# LANTERN_4LED.net
KiCad netlist of a schematic drawn in EAGLE
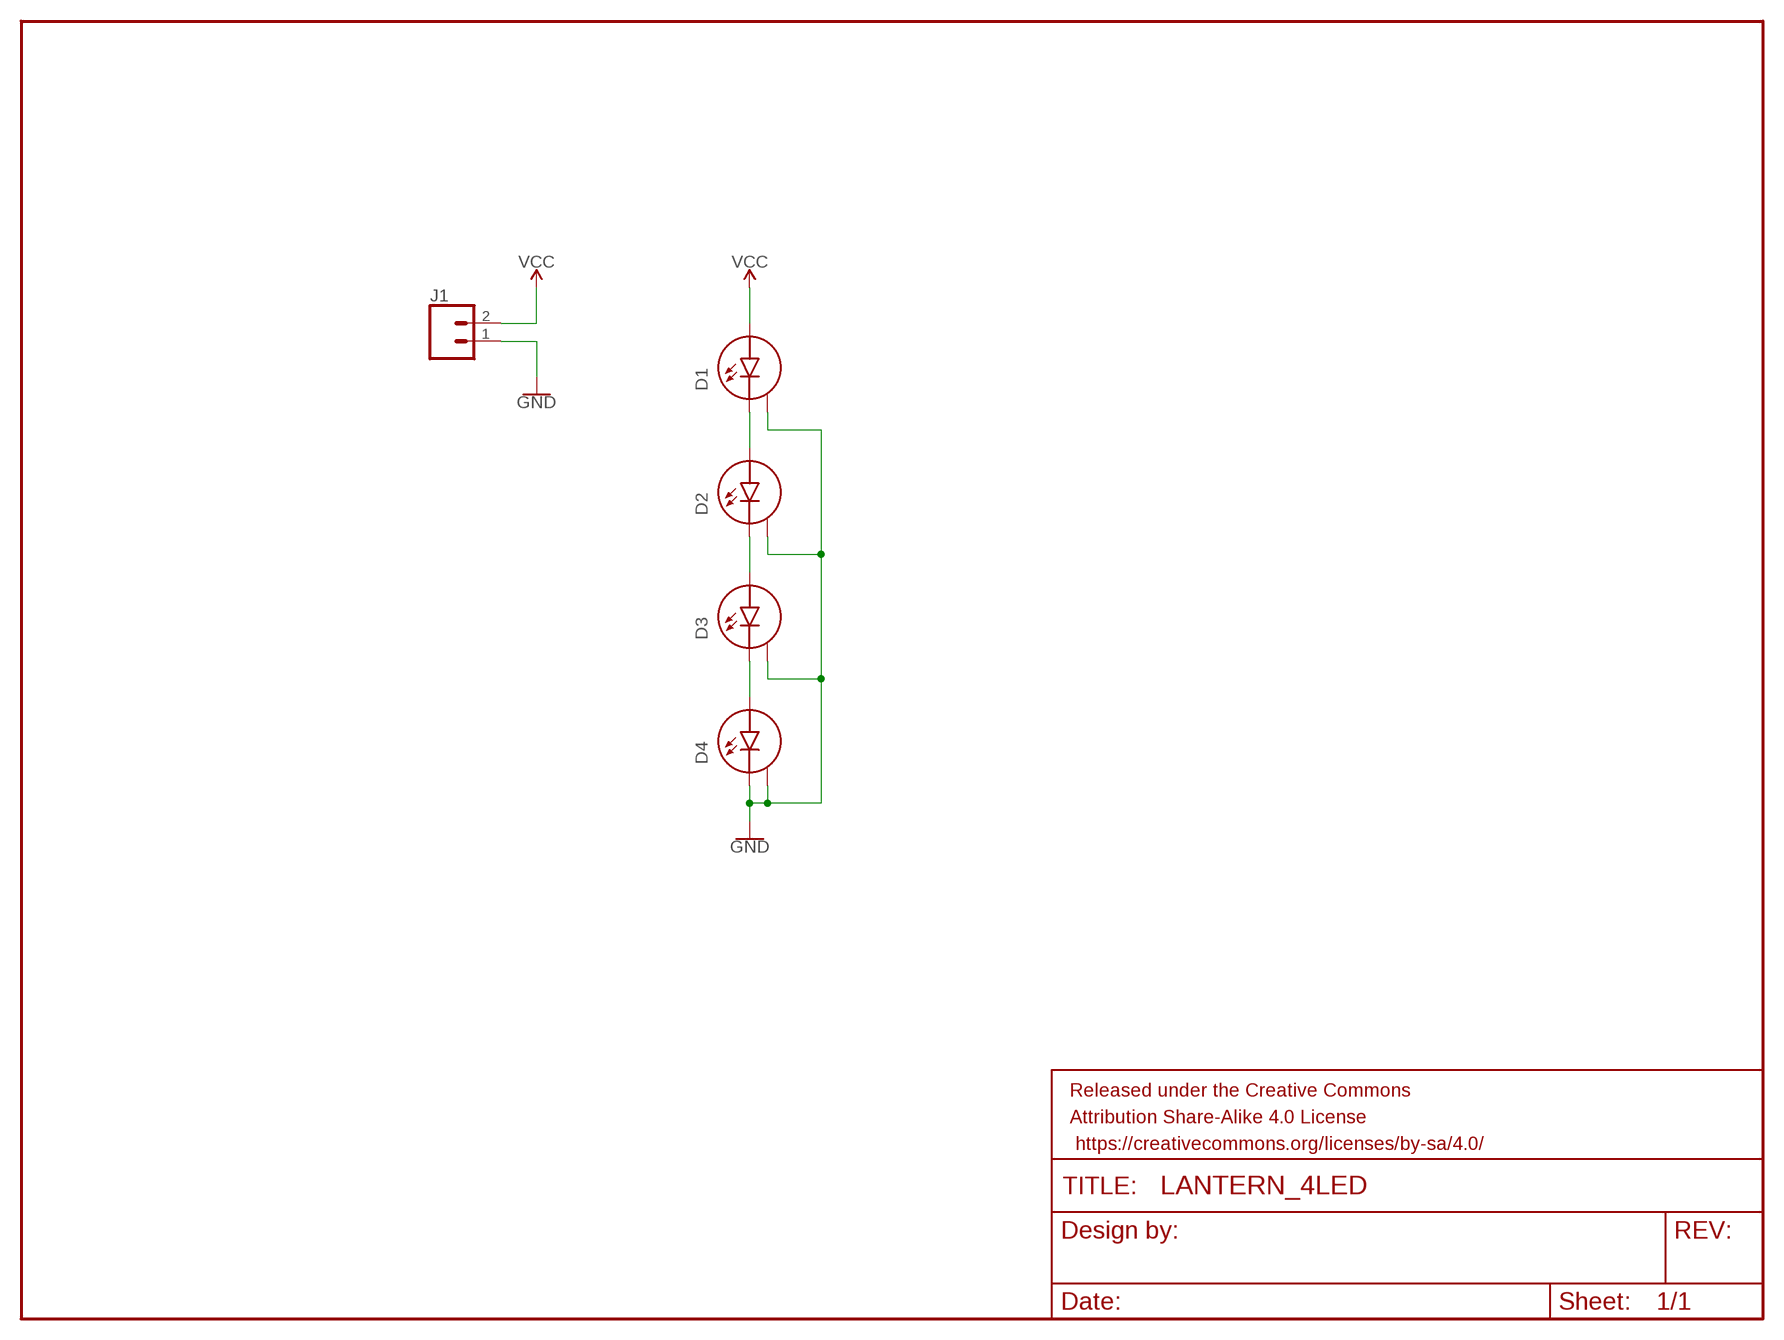
[diagram p0: schematic, sheet 1]

(export (version "E")
  (design (tool "Eeschema 10.0.6"))
  (components
    (comp (ref "D1")
      (value "LED_H1414_H")
      (footprint "eagle-import:LED_1414")
      (libsource (lib "eagle-import") (part "LED_H1414_H"))
    )
    (comp (ref "D2")
      (value "LED_H1414_H")
      (footprint "eagle-import:LED_1414")
      (libsource (lib "eagle-import") (part "LED_H1414_H"))
    )
    (comp (ref "D3")
      (value "LED_H1414_H")
      (footprint "eagle-import:LED_1414")
      (libsource (lib "eagle-import") (part "LED_H1414_H"))
    )
    (comp (ref "D4")
      (value "LED_H1414_H")
      (footprint "eagle-import:LED_1414")
      (libsource (lib "eagle-import") (part "LED_H1414_H"))
    )
    (comp (ref "FRAME1")
      (value "FRAME-LETTERNO_PACKAGE")
      (footprint "eagle-import:DUMMY")
      (fields (field (name "DESIGNER") "Nobody"))
      (libsource (lib "eagle-import") (part "FRAME-LETTERNO_PACKAGE"))
    )
    (comp (ref "J1")
      (value "CONN_02PTH3")
      (footprint "eagle-import:1X02_LONGPADS")
      (libsource (lib "eagle-import") (part "CONN_02PTH3"))
    )
  )
  (nets
    (net (code "1") (name "GND") (class "Default")
      (node (ref "D1") (pin "H") (pinfunction "H_H") (pintype "passive"))
      (node (ref "D2") (pin "H") (pinfunction "H_H") (pintype "passive"))
      (node (ref "D3") (pin "H") (pinfunction "H_H") (pintype "passive"))
      (node (ref "D4") (pin "C") (pinfunction "C_C") (pintype "passive"))
      (node (ref "D4") (pin "H") (pinfunction "H_H") (pintype "passive"))
      (node (ref "J1") (pin "1") (pinfunction "1_1") (pintype "passive"))
    )
    (net (code "2") (name "Net-(D1-PadC)") (class "Default")
      (node (ref "D1") (pin "C") (pinfunction "C_C") (pintype "passive"))
      (node (ref "D2") (pin "A") (pinfunction "A_A") (pintype "passive"))
    )
    (net (code "3") (name "Net-(D2-PadC)") (class "Default")
      (node (ref "D2") (pin "C") (pinfunction "C_C") (pintype "passive"))
      (node (ref "D3") (pin "A") (pinfunction "A_A") (pintype "passive"))
    )
    (net (code "4") (name "Net-(D3-PadC)") (class "Default")
      (node (ref "D3") (pin "C") (pinfunction "C_C") (pintype "passive"))
      (node (ref "D4") (pin "A") (pinfunction "A_A") (pintype "passive"))
    )
    (net (code "5") (name "VCC") (class "Default")
      (node (ref "D1") (pin "A") (pinfunction "A_A") (pintype "passive"))
      (node (ref "J1") (pin "2") (pinfunction "2_2") (pintype "passive"))
    )
  )
)
